# oc76_v3.net
KiCad netlist of a schematic drawn in EAGLE
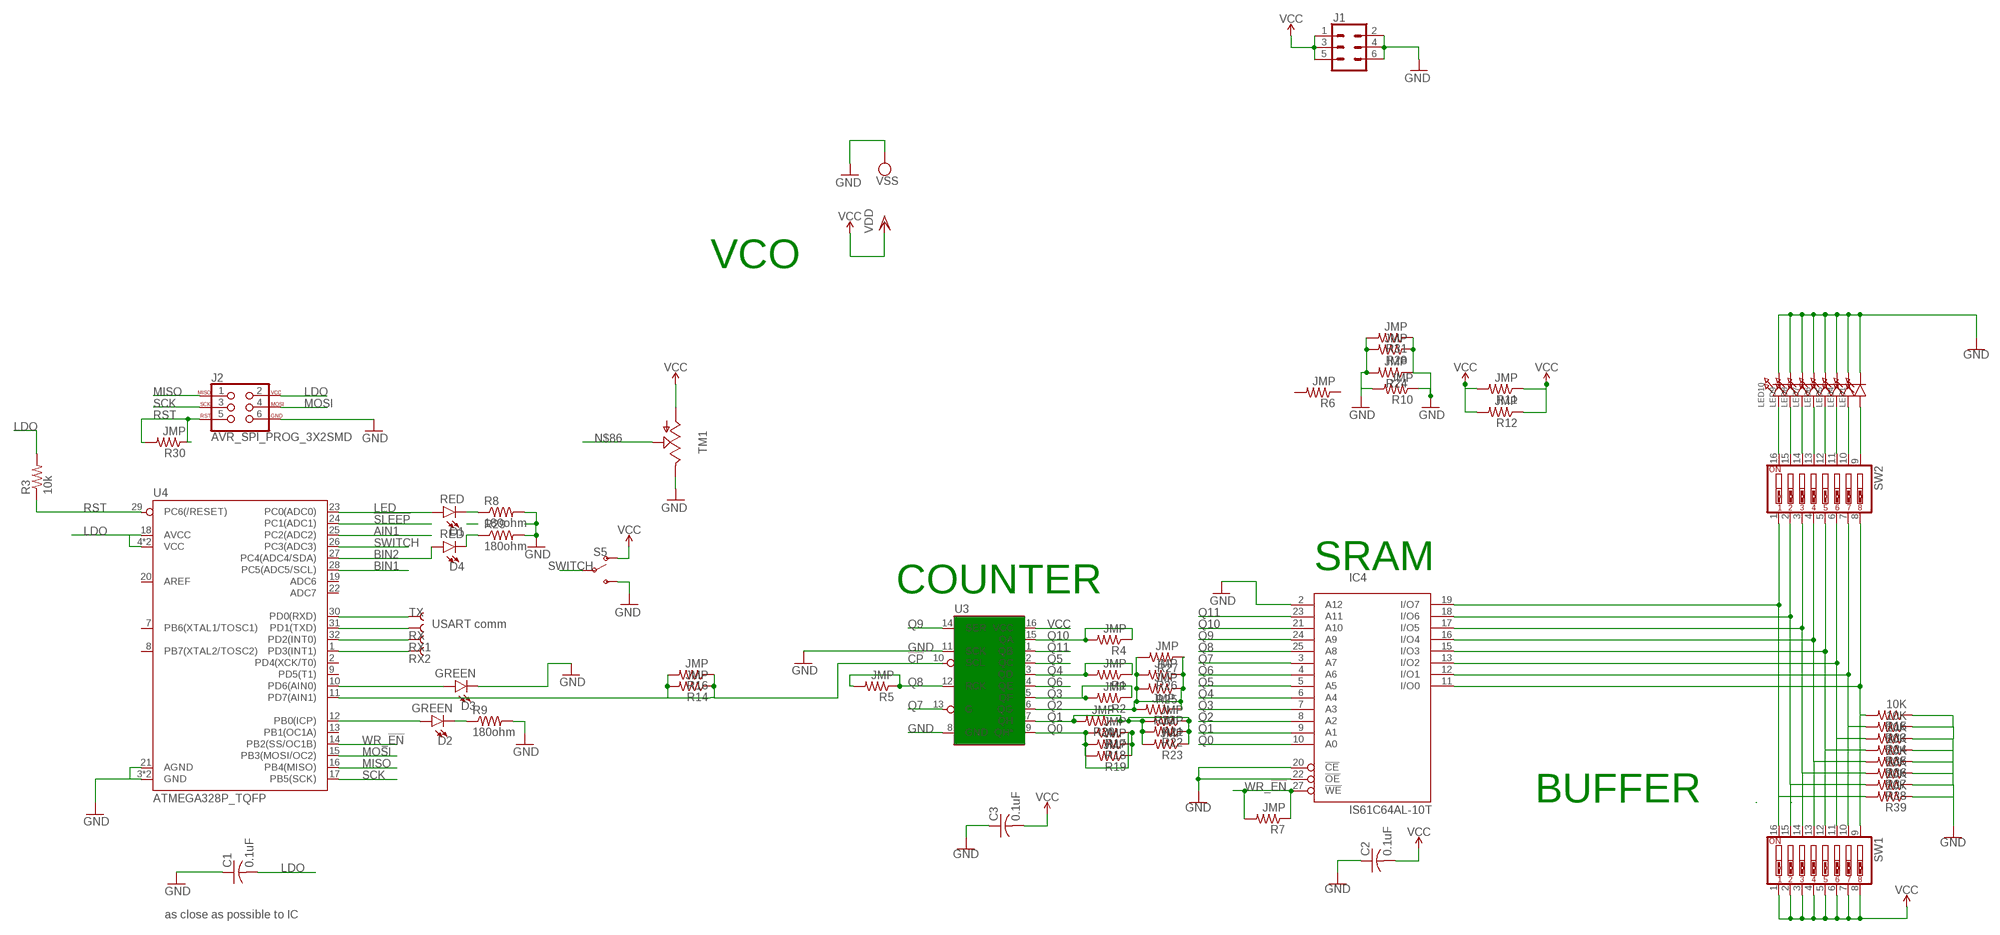
[diagram p0: schematic, sheet 1]

(export (version "E")
  (design (tool "Eeschema 10.0.6"))
  (components
    (comp (ref "C1")
      (value "0.1uF")
      (footprint "eagle-import:C1206")
      (libsource (lib "eagle-import") (part "C-USC1206"))
    )
    (comp (ref "C2")
      (value "0.1uF")
      (footprint "eagle-import:C1206")
      (libsource (lib "eagle-import") (part "C-USC1206"))
    )
    (comp (ref "C3")
      (value "0.1uF")
      (footprint "eagle-import:C1206")
      (libsource (lib "eagle-import") (part "C-USC1206"))
    )
    (comp (ref "D1")
      (value "RED")
      (footprint "eagle-import:LED-1206")
      (libsource (lib "eagle-import") (part "LED-RED1206"))
    )
    (comp (ref "D2")
      (value "GREEN")
      (footprint "eagle-import:LED-1206")
      (libsource (lib "eagle-import") (part "LED-RED1206"))
    )
    (comp (ref "D3")
      (value "GREEN")
      (footprint "eagle-import:LED-1206")
      (libsource (lib "eagle-import") (part "LED-RED1206"))
    )
    (comp (ref "D4")
      (value "RED")
      (footprint "eagle-import:LED-1206")
      (libsource (lib "eagle-import") (part "LED-RED1206"))
    )
    (comp (ref "IC4")
      (value "IS61C64AL-10T")
      (footprint "eagle-import:TSOP-I-28")
      (libsource (lib "eagle-import") (part "IS61C64AL-T10"))
    )
    (comp (ref "J1")
      (value "CONN_03X2FEMALE_SMD")
      (footprint "eagle-import:2X3_SMD")
      (libsource (lib "eagle-import") (part "CONN_03X2FEMALE_SMD"))
    )
    (comp (ref "J2")
      (value "AVR_SPI_PROG_3X2SMD")
      (footprint "eagle-import:2X3_SMT_POSTS")
      (libsource (lib "eagle-import") (part "AVR_SPI_PROG_3X2SMD"))
    )
    (comp (ref "LED1")
      (value "LED1206")
      (footprint "eagle-import:CHIPLED_1206")
      (libsource (lib "eagle-import") (part "LED1206"))
    )
    (comp (ref "LED4")
      (value "LED1206")
      (footprint "eagle-import:CHIPLED_1206")
      (libsource (lib "eagle-import") (part "LED1206"))
    )
    (comp (ref "LED5")
      (value "LED1206")
      (footprint "eagle-import:CHIPLED_1206")
      (libsource (lib "eagle-import") (part "LED1206"))
    )
    (comp (ref "LED6")
      (value "LED1206")
      (footprint "eagle-import:CHIPLED_1206")
      (libsource (lib "eagle-import") (part "LED1206"))
    )
    (comp (ref "LED7")
      (value "LED1206")
      (footprint "eagle-import:CHIPLED_1206")
      (libsource (lib "eagle-import") (part "LED1206"))
    )
    (comp (ref "LED8")
      (value "LED1206")
      (footprint "eagle-import:CHIPLED_1206")
      (libsource (lib "eagle-import") (part "LED1206"))
    )
    (comp (ref "LED9")
      (value "LED1206")
      (footprint "eagle-import:CHIPLED_1206")
      (libsource (lib "eagle-import") (part "LED1206"))
    )
    (comp (ref "LED10")
      (value "LED1206")
      (footprint "eagle-import:CHIPLED_1206")
      (libsource (lib "eagle-import") (part "LED1206"))
    )
    (comp (ref "R1")
      (value "JMP")
      (footprint "eagle-import:M1206")
      (libsource (lib "eagle-import") (part "R-US_M1206"))
    )
    (comp (ref "R2")
      (value "JMP")
      (footprint "eagle-import:M1206")
      (libsource (lib "eagle-import") (part "R-US_M1206"))
    )
    (comp (ref "R3")
      (value "10k")
      (footprint "eagle-import:R1206")
      (libsource (lib "eagle-import") (part "R-US_R1206"))
    )
    (comp (ref "R4")
      (value "JMP")
      (footprint "eagle-import:M1206")
      (libsource (lib "eagle-import") (part "R-US_M1206"))
    )
    (comp (ref "R5")
      (value "JMP")
      (footprint "eagle-import:M1206")
      (libsource (lib "eagle-import") (part "R-US_M1206"))
    )
    (comp (ref "R6")
      (value "JMP")
      (footprint "eagle-import:M1206")
      (libsource (lib "eagle-import") (part "R-US_M1206"))
    )
    (comp (ref "R7")
      (value "JMP")
      (footprint "eagle-import:M1206")
      (libsource (lib "eagle-import") (part "R-US_M1206"))
    )
    (comp (ref "R8")
      (value "180ohm")
      (footprint "eagle-import:R1206")
      (libsource (lib "eagle-import") (part "R-US_R1206"))
    )
    (comp (ref "R9")
      (value "180ohm")
      (footprint "eagle-import:R1206")
      (libsource (lib "eagle-import") (part "R-US_R1206"))
    )
    (comp (ref "R10")
      (value "JMP")
      (footprint "eagle-import:M1206")
      (libsource (lib "eagle-import") (part "R-US_M1206"))
    )
    (comp (ref "R11")
      (value "JMP")
      (footprint "eagle-import:M1206")
      (libsource (lib "eagle-import") (part "R-US_M1206"))
    )
    (comp (ref "R12")
      (value "JMP")
      (footprint "eagle-import:M1206")
      (libsource (lib "eagle-import") (part "R-US_M1206"))
    )
    (comp (ref "R13")
      (value "JMP")
      (footprint "eagle-import:M1206")
      (libsource (lib "eagle-import") (part "R-US_M1206"))
    )
    (comp (ref "R14")
      (value "JMP")
      (footprint "eagle-import:M1206")
      (libsource (lib "eagle-import") (part "R-US_M1206"))
    )
    (comp (ref "R15")
      (value "10K")
      (footprint "eagle-import:M1206")
      (libsource (lib "eagle-import") (part "R-US_M1206"))
    )
    (comp (ref "R16")
      (value "JMP")
      (footprint "eagle-import:M1206")
      (libsource (lib "eagle-import") (part "R-US_M1206"))
    )
    (comp (ref "R17")
      (value "JMP")
      (footprint "eagle-import:M1206")
      (libsource (lib "eagle-import") (part "R-US_M1206"))
    )
    (comp (ref "R18")
      (value "JMP")
      (footprint "eagle-import:M1206")
      (libsource (lib "eagle-import") (part "R-US_M1206"))
    )
    (comp (ref "R19")
      (value "JMP")
      (footprint "eagle-import:M1206")
      (libsource (lib "eagle-import") (part "R-US_M1206"))
    )
    (comp (ref "R20")
      (value "JMP")
      (footprint "eagle-import:M1206")
      (libsource (lib "eagle-import") (part "R-US_M1206"))
    )
    (comp (ref "R21")
      (value "JMP")
      (footprint "eagle-import:M1206")
      (libsource (lib "eagle-import") (part "R-US_M1206"))
    )
    (comp (ref "R22")
      (value "JMP")
      (footprint "eagle-import:M1206")
      (libsource (lib "eagle-import") (part "R-US_M1206"))
    )
    (comp (ref "R23")
      (value "JMP")
      (footprint "eagle-import:M1206")
      (libsource (lib "eagle-import") (part "R-US_M1206"))
    )
    (comp (ref "R24")
      (value "JMP")
      (footprint "eagle-import:M1206")
      (libsource (lib "eagle-import") (part "R-US_M1206"))
    )
    (comp (ref "R25")
      (value "JMP")
      (footprint "eagle-import:M1206")
      (libsource (lib "eagle-import") (part "R-US_M1206"))
    )
    (comp (ref "R26")
      (value "JMP")
      (footprint "eagle-import:M1206")
      (libsource (lib "eagle-import") (part "R-US_M1206"))
    )
    (comp (ref "R27")
      (value "JMP")
      (footprint "eagle-import:M1206")
      (libsource (lib "eagle-import") (part "R-US_M1206"))
    )
    (comp (ref "R28")
      (value "JMP")
      (footprint "eagle-import:M1206")
      (libsource (lib "eagle-import") (part "R-US_M1206"))
    )
    (comp (ref "R29")
      (value "180ohm")
      (footprint "eagle-import:R1206")
      (libsource (lib "eagle-import") (part "R-US_R1206"))
    )
    (comp (ref "R30")
      (value "JMP")
      (footprint "eagle-import:M1206")
      (libsource (lib "eagle-import") (part "R-US_M1206"))
    )
    (comp (ref "R31")
      (value "JMP")
      (footprint "eagle-import:M1206")
      (libsource (lib "eagle-import") (part "R-US_M1206"))
    )
    (comp (ref "R33")
      (value "10K")
      (footprint "eagle-import:M1206")
      (libsource (lib "eagle-import") (part "R-US_M1206"))
    )
    (comp (ref "R34")
      (value "10K")
      (footprint "eagle-import:M1206")
      (libsource (lib "eagle-import") (part "R-US_M1206"))
    )
    (comp (ref "R35")
      (value "10K")
      (footprint "eagle-import:M1206")
      (libsource (lib "eagle-import") (part "R-US_M1206"))
    )
    (comp (ref "R36")
      (value "10K")
      (footprint "eagle-import:M1206")
      (libsource (lib "eagle-import") (part "R-US_M1206"))
    )
    (comp (ref "R37")
      (value "10K")
      (footprint "eagle-import:M1206")
      (libsource (lib "eagle-import") (part "R-US_M1206"))
    )
    (comp (ref "R38")
      (value "10K")
      (footprint "eagle-import:M1206")
      (libsource (lib "eagle-import") (part "R-US_M1206"))
    )
    (comp (ref "R39")
      (value "10K")
      (footprint "eagle-import:M1206")
      (libsource (lib "eagle-import") (part "R-US_M1206"))
    )
    (comp (ref "RX")
      (value "TEST-POINT3")
      (footprint "eagle-import:PAD.03X.03")
      (libsource (lib "eagle-import") (part "TEST-POINT3"))
    )
    (comp (ref "RX1")
      (value "TEST-POINT3")
      (footprint "eagle-import:PAD.03X.03")
      (libsource (lib "eagle-import") (part "TEST-POINT3"))
    )
    (comp (ref "RX2")
      (value "TEST-POINT3")
      (footprint "eagle-import:PAD.03X.03")
      (libsource (lib "eagle-import") (part "TEST-POINT3"))
    )
    (comp (ref "S5")
      (value "SWITCH-SPDT-SMD-AYZ0202")
      (footprint "eagle-import:SWITCH_DPDT_SMD_AYZ0202")
      (libsource (lib "eagle-import") (part "SWITCH-SPDT-SMD-AYZ0202"))
    )
    (comp (ref "SW1")
      (value "DIP-08-SMT-HALFSIZE")
      (footprint "eagle-import:DIPSWITCH-08-50MIL")
      (libsource (lib "eagle-import") (part "DIP-08-SMT-HALFSIZE"))
    )
    (comp (ref "SW2")
      (value "DIP-08-SMT-HALFSIZE")
      (footprint "eagle-import:DIPSWITCH-08-50MIL")
      (libsource (lib "eagle-import") (part "DIP-08-SMT-HALFSIZE"))
    )
    (comp (ref "TM1")
      (value "TRIM")
      (footprint "eagle-import:6MM")
      (libsource (lib "eagle-import") (part "TRIM"))
    )
    (comp (ref "TX")
      (value "TEST-POINT3")
      (footprint "eagle-import:PAD.03X.03")
      (libsource (lib "eagle-import") (part "TEST-POINT3"))
    )
    (comp (ref "U3")
      (value "74595")
      (footprint "eagle-import:TSSOP16")
      (libsource (lib "eagle-import") (part "74595"))
    )
    (comp (ref "U4")
      (value "ATMEGA328P_TQFP")
      (footprint "eagle-import:TQFP32-08")
      (libsource (lib "eagle-import") (part "ATMEGA328P_TQFP"))
    )
  )
  (nets
    (net (code "1") (name "/AIN1") (class "Default")
      (node (ref "U4") (pin "25") (pinfunction "PC2(ADC2)_25") (pintype "bidirectional"))
    )
    (net (code "2") (name "/BIN1") (class "Default")
      (node (ref "U4") (pin "28") (pinfunction "PC5(ADC5/SCL)_28") (pintype "bidirectional"))
    )
    (net (code "3") (name "/BIN2") (class "Default")
      (node (ref "D4") (pin "A") (pinfunction "A_A") (pintype "passive"))
      (node (ref "U4") (pin "27") (pinfunction "PC4(ADC4/SDA)_27") (pintype "bidirectional"))
    )
    (net (code "4") (name "/LDO") (class "Default")
      (node (ref "C1") (pin "2") (pinfunction "2_2") (pintype "passive"))
      (node (ref "J2") (pin "2") (pinfunction "2_2") (pintype "passive"))
      (node (ref "R3") (pin "2") (pinfunction "2_2") (pintype "passive"))
      (node (ref "U4") (pin "18") (pinfunction "AVCC_18") (pintype "bidirectional"))
      (node (ref "U4") (pin "4") (pinfunction "VCC_4") (pintype "bidirectional"))
      (node (ref "U4") (pin "6") (pinfunction "VCC_6") (pintype "bidirectional"))
    )
    (net (code "5") (name "/LED") (class "Default")
      (node (ref "D1") (pin "A") (pinfunction "A_A") (pintype "passive"))
      (node (ref "U4") (pin "23") (pinfunction "PC0(ADC0)_23") (pintype "bidirectional"))
    )
    (net (code "6") (name "/MISO") (class "Default")
      (node (ref "J2") (pin "1") (pinfunction "1_1") (pintype "passive"))
      (node (ref "U4") (pin "16") (pinfunction "PB4(MISO)_16") (pintype "bidirectional"))
    )
    (net (code "7") (name "/MOSI") (class "Default")
      (node (ref "J2") (pin "4") (pinfunction "4_4") (pintype "passive"))
      (node (ref "U4") (pin "15") (pinfunction "PB3(MOSI/OC2)_15") (pintype "bidirectional"))
    )
    (net (code "8") (name "/N$86") (class "Default")
      (node (ref "TM1") (pin "S") (pinfunction "S_S") (pintype "passive"))
    )
    (net (code "9") (name "/Q0") (class "Default")
      (node (ref "IC4") (pin "10") (pinfunction "A0_10") (pintype "input"))
      (node (ref "R17") (pin "1") (pinfunction "1_1") (pintype "passive"))
      (node (ref "R17") (pin "2") (pinfunction "2_2") (pintype "passive"))
      (node (ref "R18") (pin "1") (pinfunction "1_1") (pintype "passive"))
      (node (ref "R18") (pin "2") (pinfunction "2_2") (pintype "passive"))
      (node (ref "R19") (pin "1") (pinfunction "1_1") (pintype "passive"))
      (node (ref "R19") (pin "2") (pinfunction "2_2") (pintype "passive"))
      (node (ref "U3") (pin "9") (pinfunction "QH*_9") (pintype "tri_state"))
    )
    (net (code "10") (name "/Q1") (class "Default")
      (node (ref "IC4") (pin "9") (pinfunction "A1_9") (pintype "input"))
      (node (ref "R20") (pin "1") (pinfunction "1_1") (pintype "passive"))
      (node (ref "R20") (pin "2") (pinfunction "2_2") (pintype "passive"))
      (node (ref "R21") (pin "1") (pinfunction "1_1") (pintype "passive"))
      (node (ref "R21") (pin "2") (pinfunction "2_2") (pintype "passive"))
      (node (ref "R22") (pin "1") (pinfunction "1_1") (pintype "passive"))
      (node (ref "R22") (pin "2") (pinfunction "2_2") (pintype "passive"))
      (node (ref "R23") (pin "1") (pinfunction "1_1") (pintype "passive"))
      (node (ref "R23") (pin "2") (pinfunction "2_2") (pintype "passive"))
      (node (ref "U3") (pin "7") (pinfunction "QH_7") (pintype "tri_state"))
    )
    (net (code "11") (name "/Q2") (class "Default")
      (node (ref "IC4") (pin "8") (pinfunction "A2_8") (pintype "input"))
      (node (ref "R13") (pin "1") (pinfunction "1_1") (pintype "passive"))
      (node (ref "R13") (pin "2") (pinfunction "2_2") (pintype "passive"))
      (node (ref "R25") (pin "1") (pinfunction "1_1") (pintype "passive"))
      (node (ref "R25") (pin "2") (pinfunction "2_2") (pintype "passive"))
      (node (ref "R26") (pin "1") (pinfunction "1_1") (pintype "passive"))
      (node (ref "R26") (pin "2") (pinfunction "2_2") (pintype "passive"))
      (node (ref "R27") (pin "1") (pinfunction "1_1") (pintype "passive"))
      (node (ref "R27") (pin "2") (pinfunction "2_2") (pintype "passive"))
      (node (ref "U3") (pin "6") (pinfunction "QG_6") (pintype "tri_state"))
    )
    (net (code "12") (name "/Q3") (class "Default")
      (node (ref "IC4") (pin "7") (pinfunction "A3_7") (pintype "input"))
      (node (ref "R2") (pin "1") (pinfunction "1_1") (pintype "passive"))
      (node (ref "R2") (pin "2") (pinfunction "2_2") (pintype "passive"))
      (node (ref "U3") (pin "5") (pinfunction "QF_5") (pintype "tri_state"))
    )
    (net (code "13") (name "/Q4") (class "Default")
      (node (ref "IC4") (pin "6") (pinfunction "A4_6") (pintype "input"))
      (node (ref "R1") (pin "1") (pinfunction "1_1") (pintype "passive"))
      (node (ref "R1") (pin "2") (pinfunction "2_2") (pintype "passive"))
      (node (ref "U3") (pin "3") (pinfunction "QD_3") (pintype "tri_state"))
    )
    (net (code "14") (name "/Q5") (class "Default")
      (node (ref "IC4") (pin "5") (pinfunction "A5_5") (pintype "input"))
      (node (ref "U3") (pin "2") (pinfunction "QC_2") (pintype "tri_state"))
    )
    (net (code "15") (name "/Q6") (class "Default")
      (node (ref "IC4") (pin "4") (pinfunction "A6_4") (pintype "input"))
      (node (ref "U3") (pin "4") (pinfunction "QE_4") (pintype "tri_state"))
    )
    (net (code "16") (name "/Q7") (class "Default")
      (node (ref "IC4") (pin "3") (pinfunction "A7_3") (pintype "input"))
      (node (ref "U3") (pin "13") (pinfunction "G_13") (pintype "input"))
    )
    (net (code "17") (name "/Q8") (class "Default")
      (node (ref "IC4") (pin "25") (pinfunction "A8_25") (pintype "input"))
      (node (ref "R5") (pin "1") (pinfunction "1_1") (pintype "passive"))
      (node (ref "R5") (pin "2") (pinfunction "2_2") (pintype "passive"))
      (node (ref "U3") (pin "12") (pinfunction "RCK_12") (pintype "input"))
    )
    (net (code "18") (name "/Q9") (class "Default")
      (node (ref "IC4") (pin "24") (pinfunction "A9_24") (pintype "input"))
      (node (ref "U3") (pin "14") (pinfunction "SER_14") (pintype "input"))
    )
    (net (code "19") (name "/Q10") (class "Default")
      (node (ref "IC4") (pin "21") (pinfunction "A10_21") (pintype "input"))
      (node (ref "R4") (pin "1") (pinfunction "1_1") (pintype "passive"))
      (node (ref "R4") (pin "2") (pinfunction "2_2") (pintype "passive"))
      (node (ref "U3") (pin "15") (pinfunction "QA_15") (pintype "tri_state"))
    )
    (net (code "20") (name "/Q11") (class "Default")
      (node (ref "IC4") (pin "23") (pinfunction "A11_23") (pintype "input"))
      (node (ref "U3") (pin "1") (pinfunction "QB_1") (pintype "tri_state"))
    )
    (net (code "21") (name "/RST") (class "Default")
      (node (ref "J2") (pin "5") (pinfunction "5_5") (pintype "passive"))
      (node (ref "R3") (pin "1") (pinfunction "1_1") (pintype "passive"))
      (node (ref "R30") (pin "1") (pinfunction "1_1") (pintype "passive"))
      (node (ref "R30") (pin "2") (pinfunction "2_2") (pintype "passive"))
      (node (ref "U4") (pin "29") (pinfunction "PC6(/RESET)_29") (pintype "bidirectional"))
    )
    (net (code "22") (name "/SCK") (class "Default")
      (node (ref "J2") (pin "3") (pinfunction "3_3") (pintype "passive"))
      (node (ref "U4") (pin "17") (pinfunction "PB5(SCK)_17") (pintype "bidirectional"))
    )
    (net (code "23") (name "/SWITCH") (class "Default")
      (node (ref "S5") (pin "2") (pinfunction "P_2") (pintype "passive"))
      (node (ref "U4") (pin "26") (pinfunction "PC3(ADC3)_26") (pintype "bidirectional"))
    )
    (net (code "24") (name "/WR_~{EN}") (class "Default")
      (node (ref "IC4") (pin "27") (pinfunction "~{WE}_27") (pintype "input"))
      (node (ref "R7") (pin "1") (pinfunction "1_1") (pintype "passive"))
      (node (ref "R7") (pin "2") (pinfunction "2_2") (pintype "passive"))
      (node (ref "U4") (pin "14") (pinfunction "PB2(SS/OC1B)_14") (pintype "bidirectional"))
    )
    (net (code "25") (name "/~{CP}") (class "Default")
      (node (ref "R14") (pin "1") (pinfunction "1_1") (pintype "passive"))
      (node (ref "R14") (pin "2") (pinfunction "2_2") (pintype "passive"))
      (node (ref "R16") (pin "1") (pinfunction "1_1") (pintype "passive"))
      (node (ref "R16") (pin "2") (pinfunction "2_2") (pintype "passive"))
      (node (ref "U3") (pin "10") (pinfunction "SCL_10") (pintype "input"))
      (node (ref "U4") (pin "11") (pinfunction "PD7(AIN1)_11") (pintype "bidirectional"))
    )
    (net (code "26") (name "/~{SLEEP}") (class "Default")
      (node (ref "U4") (pin "24") (pinfunction "PC1(ADC1)_24") (pintype "bidirectional"))
    )
    (net (code "27") (name "GND") (class "Default")
      (node (ref "C1") (pin "1") (pinfunction "1_1") (pintype "passive"))
      (node (ref "C2") (pin "1") (pinfunction "1_1") (pintype "passive"))
      (node (ref "C3") (pin "1") (pinfunction "1_1") (pintype "passive"))
      (node (ref "D3") (pin "C") (pinfunction "C_C") (pintype "passive"))
      (node (ref "IC4") (pin "2") (pinfunction "A12_2") (pintype "input"))
      (node (ref "IC4") (pin "20") (pinfunction "~{CE}_20") (pintype "input"))
      (node (ref "IC4") (pin "22") (pinfunction "~{OE}_22") (pintype "input"))
      (node (ref "J1") (pin "2") (pinfunction "2_2") (pintype "bidirectional"))
      (node (ref "J1") (pin "4") (pinfunction "4_4") (pintype "bidirectional"))
      (node (ref "J1") (pin "6") (pinfunction "6_6") (pintype "bidirectional"))
      (node (ref "J2") (pin "6") (pinfunction "6_6") (pintype "passive"))
      (node (ref "LED1") (pin "C") (pinfunction "C_C") (pintype "passive"))
      (node (ref "LED10") (pin "C") (pinfunction "C_C") (pintype "passive"))
      (node (ref "LED4") (pin "C") (pinfunction "C_C") (pintype "passive"))
      (node (ref "LED5") (pin "C") (pinfunction "C_C") (pintype "passive"))
      (node (ref "LED6") (pin "C") (pinfunction "C_C") (pintype "passive"))
      (node (ref "LED7") (pin "C") (pinfunction "C_C") (pintype "passive"))
      (node (ref "LED8") (pin "C") (pinfunction "C_C") (pintype "passive"))
      (node (ref "LED9") (pin "C") (pinfunction "C_C") (pintype "passive"))
      (node (ref "R10") (pin "1") (pinfunction "1_1") (pintype "passive"))
      (node (ref "R10") (pin "2") (pinfunction "2_2") (pintype "passive"))
      (node (ref "R15") (pin "1") (pinfunction "1_1") (pintype "passive"))
      (node (ref "R24") (pin "1") (pinfunction "1_1") (pintype "passive"))
      (node (ref "R24") (pin "2") (pinfunction "2_2") (pintype "passive"))
      (node (ref "R28") (pin "1") (pinfunction "1_1") (pintype "passive"))
      (node (ref "R28") (pin "2") (pinfunction "2_2") (pintype "passive"))
      (node (ref "R29") (pin "2") (pinfunction "2_2") (pintype "passive"))
      (node (ref "R31") (pin "1") (pinfunction "1_1") (pintype "passive"))
      (node (ref "R31") (pin "2") (pinfunction "2_2") (pintype "passive"))
      (node (ref "R33") (pin "1") (pinfunction "1_1") (pintype "passive"))
      (node (ref "R34") (pin "1") (pinfunction "1_1") (pintype "passive"))
      (node (ref "R35") (pin "1") (pinfunction "1_1") (pintype "passive"))
      (node (ref "R36") (pin "1") (pinfunction "1_1") (pintype "passive"))
      (node (ref "R37") (pin "1") (pinfunction "1_1") (pintype "passive"))
      (node (ref "R38") (pin "1") (pinfunction "1_1") (pintype "passive"))
      (node (ref "R39") (pin "1") (pinfunction "1_1") (pintype "passive"))
      (node (ref "R8") (pin "2") (pinfunction "2_2") (pintype "passive"))
      (node (ref "R9") (pin "2") (pinfunction "2_2") (pintype "passive"))
      (node (ref "S5") (pin "3") (pinfunction "S_3") (pintype "passive"))
      (node (ref "TM1") (pin "E") (pinfunction "E_E") (pintype "passive"))
      (node (ref "U3") (pin "11") (pinfunction "SCK_11") (pintype "input"))
      (node (ref "U3") (pin "8") (pinfunction "GND_8") (pintype "power_in"))
      (node (ref "U4") (pin "21") (pinfunction "AGND_21") (pintype "bidirectional"))
      (node (ref "U4") (pin "3") (pinfunction "GND_3") (pintype "bidirectional"))
      (node (ref "U4") (pin "5") (pinfunction "GND_5") (pintype "bidirectional"))
    )
    (net (code "28") (name "Net-(D1-PadC)") (class "Default")
      (node (ref "D1") (pin "C") (pinfunction "C_C") (pintype "passive"))
      (node (ref "R8") (pin "1") (pinfunction "1_1") (pintype "passive"))
    )
    (net (code "29") (name "Net-(D2-PadC)") (class "Default")
      (node (ref "D2") (pin "C") (pinfunction "C_C") (pintype "passive"))
      (node (ref "R9") (pin "1") (pinfunction "1_1") (pintype "passive"))
    )
    (net (code "30") (name "Net-(D4-PadC)") (class "Default")
      (node (ref "D4") (pin "C") (pinfunction "C_C") (pintype "passive"))
      (node (ref "R29") (pin "1") (pinfunction "1_1") (pintype "passive"))
    )
    (net (code "31") (name "Net-(IC4B-I{slash}O0)") (class "Default")
      (node (ref "IC4") (pin "11") (pinfunction "I/O0_11") (pintype "tri_state"))
      (node (ref "R15") (pin "2") (pinfunction "2_2") (pintype "passive"))
      (node (ref "SW1") (pin "9") (pinfunction "9_9") (pintype "passive"))
      (node (ref "SW2") (pin "8") (pinfunction "8_8") (pintype "passive"))
    )
    (net (code "32") (name "Net-(IC4B-I{slash}O1)") (class "Default")
      (node (ref "IC4") (pin "12") (pinfunction "I/O1_12") (pintype "tri_state"))
      (node (ref "R33") (pin "2") (pinfunction "2_2") (pintype "passive"))
      (node (ref "SW1") (pin "10") (pinfunction "10_10") (pintype "passive"))
      (node (ref "SW2") (pin "7") (pinfunction "7_7") (pintype "passive"))
    )
    (net (code "33") (name "Net-(IC4B-I{slash}O2)") (class "Default")
      (node (ref "IC4") (pin "13") (pinfunction "I/O2_13") (pintype "tri_state"))
      (node (ref "R34") (pin "2") (pinfunction "2_2") (pintype "passive"))
      (node (ref "SW1") (pin "11") (pinfunction "11_11") (pintype "passive"))
      (node (ref "SW2") (pin "6") (pinfunction "6_6") (pintype "passive"))
    )
    (net (code "34") (name "Net-(IC4B-I{slash}O3)") (class "Default")
      (node (ref "IC4") (pin "15") (pinfunction "I/O3_15") (pintype "tri_state"))
      (node (ref "R35") (pin "2") (pinfunction "2_2") (pintype "passive"))
      (node (ref "SW1") (pin "12") (pinfunction "12_12") (pintype "passive"))
      (node (ref "SW2") (pin "5") (pinfunction "5_5") (pintype "passive"))
    )
    (net (code "35") (name "Net-(IC4B-I{slash}O4)") (class "Default")
      (node (ref "IC4") (pin "16") (pinfunction "I/O4_16") (pintype "tri_state"))
      (node (ref "R36") (pin "2") (pinfunction "2_2") (pintype "passive"))
      (node (ref "SW1") (pin "13") (pinfunction "13_13") (pintype "passive"))
      (node (ref "SW2") (pin "4") (pinfunction "4_4") (pintype "passive"))
    )
    (net (code "36") (name "Net-(IC4B-I{slash}O5)") (class "Default")
      (node (ref "IC4") (pin "17") (pinfunction "I/O5_17") (pintype "tri_state"))
      (node (ref "R37") (pin "2") (pinfunction "2_2") (pintype "passive"))
      (node (ref "SW1") (pin "14") (pinfunction "14_14") (pintype "passive"))
      (node (ref "SW2") (pin "3") (pinfunction "3_3") (pintype "passive"))
    )
    (net (code "37") (name "Net-(IC4B-I{slash}O6)") (class "Default")
      (node (ref "IC4") (pin "18") (pinfunction "I/O6_18") (pintype "tri_state"))
      (node (ref "R38") (pin "2") (pinfunction "2_2") (pintype "passive"))
      (node (ref "SW1") (pin "15") (pinfunction "15_15") (pintype "passive"))
      (node (ref "SW2") (pin "2") (pinfunction "2_2") (pintype "passive"))
    )
    (net (code "38") (name "Net-(IC4B-I{slash}O7)") (class "Default")
      (node (ref "IC4") (pin "19") (pinfunction "I/O7_19") (pintype "tri_state"))
      (node (ref "R39") (pin "2") (pinfunction "2_2") (pintype "passive"))
      (node (ref "SW1") (pin "16") (pinfunction "16_16") (pintype "passive"))
      (node (ref "SW2") (pin "1") (pinfunction "1_1") (pintype "passive"))
    )
    (net (code "39") (name "Net-(LED1-PadA)") (class "Default")
      (node (ref "LED1") (pin "A") (pinfunction "A_A") (pintype "passive"))
      (node (ref "SW2") (pin "9") (pinfunction "9_9") (pintype "passive"))
    )
    (net (code "40") (name "Net-(LED4-PadA)") (class "Default")
      (node (ref "LED4") (pin "A") (pinfunction "A_A") (pintype "passive"))
      (node (ref "SW2") (pin "10") (pinfunction "10_10") (pintype "passive"))
    )
    (net (code "41") (name "Net-(LED5-PadA)") (class "Default")
      (node (ref "LED5") (pin "A") (pinfunction "A_A") (pintype "passive"))
      (node (ref "SW2") (pin "11") (pinfunction "11_11") (pintype "passive"))
    )
    (net (code "42") (name "Net-(LED6-PadA)") (class "Default")
      (node (ref "LED6") (pin "A") (pinfunction "A_A") (pintype "passive"))
      (node (ref "SW2") (pin "12") (pinfunction "12_12") (pintype "passive"))
    )
    (net (code "43") (name "Net-(LED7-PadA)") (class "Default")
      (node (ref "LED7") (pin "A") (pinfunction "A_A") (pintype "passive"))
      (node (ref "SW2") (pin "13") (pinfunction "13_13") (pintype "passive"))
    )
    (net (code "44") (name "Net-(LED8-PadA)") (class "Default")
      (node (ref "LED8") (pin "A") (pinfunction "A_A") (pintype "passive"))
      (node (ref "SW2") (pin "14") (pinfunction "14_14") (pintype "passive"))
    )
    (net (code "45") (name "Net-(LED9-PadA)") (class "Default")
      (node (ref "LED9") (pin "A") (pinfunction "A_A") (pintype "passive"))
      (node (ref "SW2") (pin "15") (pinfunction "15_15") (pintype "passive"))
    )
    (net (code "46") (name "Net-(LED10-PadA)") (class "Default")
      (node (ref "LED10") (pin "A") (pinfunction "A_A") (pintype "passive"))
      (node (ref "SW2") (pin "16") (pinfunction "16_16") (pintype "passive"))
    )
    (net (code "47") (name "Net-(RX-1)") (class "Default")
      (node (ref "RX") (pin "P$1") (pinfunction "1_P$1") (pintype "bidirectional"))
      (node (ref "U4") (pin "31") (pinfunction "PD1(TXD)_31") (pintype "bidirectional"))
    )
    (net (code "48") (name "Net-(RX1-1)") (class "Default")
      (node (ref "RX1") (pin "P$1") (pinfunction "1_P$1") (pintype "bidirectional"))
      (node (ref "U4") (pin "32") (pinfunction "PD2(INT0)_32") (pintype "bidirectional"))
    )
    (net (code "49") (name "Net-(RX2-1)") (class "Default")
      (node (ref "RX2") (pin "P$1") (pinfunction "1_P$1") (pintype "bidirectional"))
      (node (ref "U4") (pin "1") (pinfunction "PD3(INT1)_1") (pintype "bidirectional"))
    )
    (net (code "50") (name "Net-(TX-1)") (class "Default")
      (node (ref "TX") (pin "P$1") (pinfunction "1_P$1") (pintype "bidirectional"))
      (node (ref "U4") (pin "30") (pinfunction "PD0(RXD)_30") (pintype "bidirectional"))
    )
    (net (code "51") (name "Net-(U4-PB0(ICP))") (class "Default")
      (node (ref "D2") (pin "A") (pinfunction "A_A") (pintype "passive"))
      (node (ref "U4") (pin "12") (pinfunction "PB0(ICP)_12") (pintype "bidirectional"))
    )
    (net (code "52") (name "Net-(U4-PD6(AIN0))") (class "Default")
      (node (ref "D3") (pin "A") (pinfunction "A_A") (pintype "passive"))
      (node (ref "U4") (pin "10") (pinfunction "PD6(AIN0)_10") (pintype "bidirectional"))
    )
    (net (code "53") (name "VCC") (class "Default")
      (node (ref "C2") (pin "2") (pinfunction "2_2") (pintype "passive"))
      (node (ref "C3") (pin "2") (pinfunction "2_2") (pintype "passive"))
      (node (ref "J1") (pin "1") (pinfunction "1_1") (pintype "bidirectional"))
      (node (ref "J1") (pin "3") (pinfunction "3_3") (pintype "bidirectional"))
      (node (ref "J1") (pin "5") (pinfunction "5_5") (pintype "bidirectional"))
      (node (ref "R11") (pin "1") (pinfunction "1_1") (pintype "passive"))
      (node (ref "R11") (pin "2") (pinfunction "2_2") (pintype "passive"))
      (node (ref "R12") (pin "1") (pinfunction "1_1") (pintype "passive"))
      (node (ref "R12") (pin "2") (pinfunction "2_2") (pintype "passive"))
      (node (ref "S5") (pin "1") (pinfunction "O_1") (pintype "passive"))
      (node (ref "SW1") (pin "1") (pinfunction "1_1") (pintype "passive"))
      (node (ref "SW1") (pin "2") (pinfunction "2_2") (pintype "passive"))
      (node (ref "SW1") (pin "3") (pinfunction "3_3") (pintype "passive"))
      (node (ref "SW1") (pin "4") (pinfunction "4_4") (pintype "passive"))
      (node (ref "SW1") (pin "5") (pinfunction "5_5") (pintype "passive"))
      (node (ref "SW1") (pin "6") (pinfunction "6_6") (pintype "passive"))
      (node (ref "SW1") (pin "7") (pinfunction "7_7") (pintype "passive"))
      (node (ref "SW1") (pin "8") (pinfunction "8_8") (pintype "passive"))
      (node (ref "TM1") (pin "A") (pinfunction "A_A") (pintype "passive"))
      (node (ref "U3") (pin "16") (pinfunction "VCC_16") (pintype "power_in"))
    )
    (net (code "54") (name "unconnected-(R6-Pad1)") (class "Default")
      (node (ref "R6") (pin "1") (pinfunction "1_1") (pintype "passive"))
    )
    (net (code "55") (name "unconnected-(R6-Pad2)") (class "Default")
      (node (ref "R6") (pin "2") (pinfunction "2_2") (pintype "passive"))
    )
    (net (code "56") (name "unconnected-(U4-ADC6-Pad19)") (class "Default")
      (node (ref "U4") (pin "19") (pinfunction "ADC6_19") (pintype "bidirectional"))
    )
    (net (code "57") (name "unconnected-(U4-ADC7-Pad22)") (class "Default")
      (node (ref "U4") (pin "22") (pinfunction "ADC7_22") (pintype "bidirectional"))
    )
    (net (code "58") (name "unconnected-(U4-AREF-Pad20)") (class "Default")
      (node (ref "U4") (pin "20") (pinfunction "AREF_20") (pintype "bidirectional"))
    )
    (net (code "59") (name "unconnected-(U4-PB1(OC1A)-Pad13)") (class "Default")
      (node (ref "U4") (pin "13") (pinfunction "PB1(OC1A)_13") (pintype "bidirectional"))
    )
    (net (code "60") (name "unconnected-(U4-PB6(XTAL1{slash}TOSC1)-Pad7)") (class "Default")
      (node (ref "U4") (pin "7") (pinfunction "PB6(XTAL1/TOSC1)_7") (pintype "bidirectional"))
    )
    (net (code "61") (name "unconnected-(U4-PB7(XTAL2{slash}TOSC2)-Pad8)") (class "Default")
      (node (ref "U4") (pin "8") (pinfunction "PB7(XTAL2/TOSC2)_8") (pintype "bidirectional"))
    )
    (net (code "62") (name "unconnected-(U4-PD4(XCK{slash}T0)-Pad2)") (class "Default")
      (node (ref "U4") (pin "2") (pinfunction "PD4(XCK/T0)_2") (pintype "bidirectional"))
    )
    (net (code "63") (name "unconnected-(U4-PD5(T1)-Pad9)") (class "Default")
      (node (ref "U4") (pin "9") (pinfunction "PD5(T1)_9") (pintype "bidirectional"))
    )
  )
)
